# IM920Sender.net
KiCad netlist of a schematic drawn in EAGLE
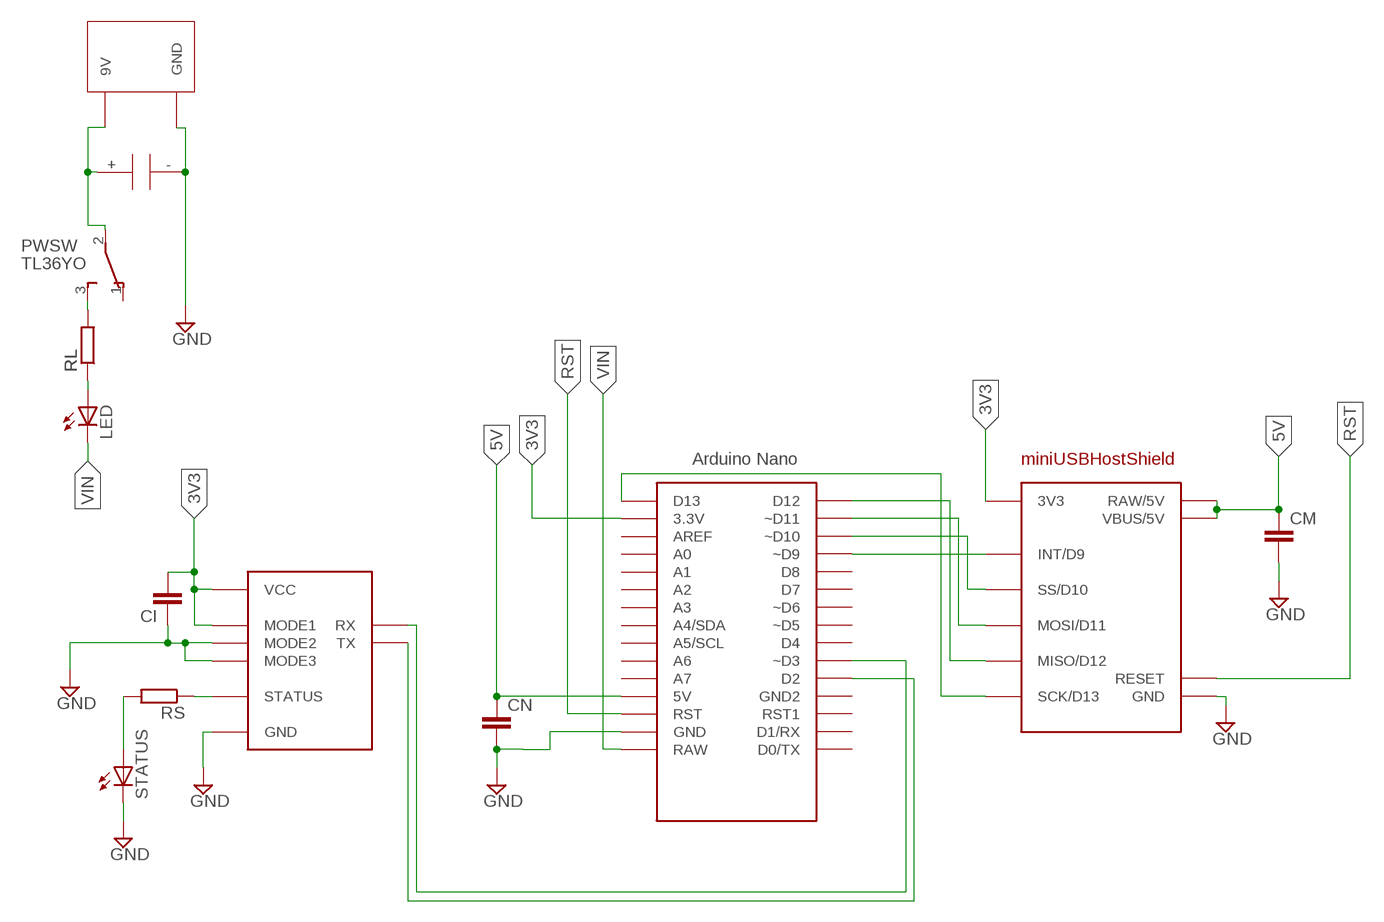
[diagram p0: schematic, sheet 1]

(export (version "E")
  (design (tool "Eeschema 10.0.6"))
  (components
    (comp (ref "CI")
      (value "C2.5/2")
      (footprint "eagle-import:C2.5-2")
      (libsource (lib "eagle-import") (part "C2.5/2"))
    )
    (comp (ref "CM")
      (value "C2.5/2")
      (footprint "eagle-import:C2.5-2")
      (libsource (lib "eagle-import") (part "C2.5/2"))
    )
    (comp (ref "CN")
      (value "C2.5/2")
      (footprint "eagle-import:C2.5-2")
      (libsource (lib "eagle-import") (part "C2.5/2"))
    )
    (comp (ref "LED")
      (value "LED3MM")
      (footprint "eagle-import:LED3MM")
      (libsource (lib "eagle-import") (part "LED3MM"))
    )
    (comp (ref "PWSW")
      (value "TL36YO")
      (footprint "eagle-import:TL3XYO")
      (libsource (lib "eagle-import") (part "TL36YO"))
    )
    (comp (ref "RL")
      (value "R-EU_0204/7")
      (footprint "eagle-import:0204_7")
      (libsource (lib "eagle-import") (part "R-EU_0204/7"))
    )
    (comp (ref "RS")
      (value "R-EU_0204/7")
      (footprint "eagle-import:0204_7")
      (libsource (lib "eagle-import") (part "R-EU_0204/7"))
    )
    (comp (ref "STATUS")
      (value "LED3MM")
      (footprint "eagle-import:LED3MM")
      (libsource (lib "eagle-import") (part "LED3MM"))
    )
    (comp (ref "U$1")
      (value "IM920")
      (footprint "eagle-import:IM920")
      (libsource (lib "eagle-import") (part "IM920"))
    )
    (comp (ref "U$2")
      (value "BH-9V-1P")
      (footprint "eagle-import:BH-9V-1P")
      (libsource (lib "eagle-import") (part "BH-9V-1P"))
    )
    (comp (ref "U$4")
      (value "MINI-USBHOSTSHIELD")
      (footprint "eagle-import:USBMINI")
      (libsource (lib "eagle-import") (part "MINI-USBHOSTSHIELD"))
    )
    (comp (ref "U$5")
      (value "C-10U")
      (footprint "eagle-import:C-10U")
      (libsource (lib "eagle-import") (part "C-10U"))
    )
    (comp (ref "U$6")
      (value "NANO")
      (footprint "eagle-import:NANO")
      (libsource (lib "eagle-import") (part "NANO"))
    )
  )
  (nets
    (net (code "1") (name "3V3") (class "Default")
      (node (ref "CI") (pin "2") (pinfunction "2_2") (pintype "passive"))
      (node (ref "U$1") (pin "MODE1") (pinfunction "MODE1_MODE1") (pintype "bidirectional"))
      (node (ref "U$1") (pin "VCC") (pinfunction "VCC_VCC") (pintype "bidirectional"))
      (node (ref "U$4") (pin "3V3") (pinfunction "3V3_3V3") (pintype "bidirectional"))
      (node (ref "U$6") (pin "3.3V") (pinfunction "3.3V_3.3V") (pintype "bidirectional"))
    )
    (net (code "2") (name "5V") (class "Default")
      (node (ref "CM") (pin "1") (pinfunction "1_1") (pintype "passive"))
      (node (ref "CN") (pin "1") (pinfunction "1_1") (pintype "passive"))
      (node (ref "U$4") (pin "RAW") (pinfunction "RAW/5V_RAW") (pintype "bidirectional"))
      (node (ref "U$4") (pin "VBUS") (pinfunction "VBUS/5V_VBUS") (pintype "bidirectional"))
      (node (ref "U$6") (pin "5V") (pinfunction "5V_5V") (pintype "bidirectional"))
    )
    (net (code "3") (name "GND") (class "Default")
      (node (ref "CI") (pin "1") (pinfunction "1_1") (pintype "passive"))
      (node (ref "CM") (pin "2") (pinfunction "2_2") (pintype "passive"))
      (node (ref "CN") (pin "2") (pinfunction "2_2") (pintype "passive"))
      (node (ref "STATUS") (pin "K") (pinfunction "C_K") (pintype "passive"))
      (node (ref "U$1") (pin "GND") (pinfunction "GND_GND") (pintype "bidirectional"))
      (node (ref "U$1") (pin "MODE2") (pinfunction "MODE2_MODE2") (pintype "bidirectional"))
      (node (ref "U$1") (pin "MODE3") (pinfunction "MODE3_MODE3") (pintype "bidirectional"))
      (node (ref "U$2") (pin "GND") (pinfunction "GND_GND") (pintype "bidirectional"))
      (node (ref "U$4") (pin "GND") (pinfunction "GND_GND") (pintype "bidirectional"))
      (node (ref "U$4") (pin "GND1") (pinfunction "GND_GND1") (pintype "bidirectional"))
      (node (ref "U$5") (pin "-") (pinfunction "-_-") (pintype "bidirectional"))
      (node (ref "U$6") (pin "GND") (pinfunction "GND_GND") (pintype "bidirectional"))
    )
    (net (code "4") (name "Net-(LED-PadA)") (class "Default")
      (node (ref "LED") (pin "A") (pinfunction "A_A") (pintype "passive"))
      (node (ref "RL") (pin "1") (pinfunction "1_1") (pintype "passive"))
    )
    (net (code "5") (name "Net-(PWSW-P)") (class "Default")
      (node (ref "PWSW") (pin "2") (pinfunction "P_2") (pintype "passive"))
      (node (ref "U$2") (pin "9V") (pinfunction "9V_9V") (pintype "bidirectional"))
      (node (ref "U$5") (pin "+") (pinfunction "+_+") (pintype "bidirectional"))
    )
    (net (code "6") (name "Net-(PWSW-S)") (class "Default")
      (node (ref "PWSW") (pin "3") (pinfunction "S_3") (pintype "passive"))
      (node (ref "RL") (pin "2") (pinfunction "2_2") (pintype "passive"))
    )
    (net (code "7") (name "Net-(RS-Pad1)") (class "Default")
      (node (ref "RS") (pin "1") (pinfunction "1_1") (pintype "passive"))
      (node (ref "U$1") (pin "STATUS") (pinfunction "STATUS_STATUS") (pintype "bidirectional"))
    )
    (net (code "8") (name "Net-(RS-Pad2)") (class "Default")
      (node (ref "RS") (pin "2") (pinfunction "2_2") (pintype "passive"))
      (node (ref "STATUS") (pin "A") (pinfunction "A_A") (pintype "passive"))
    )
    (net (code "9") (name "Net-(U$1-PadTX)") (class "Default")
      (node (ref "U$1") (pin "TX") (pinfunction "TX_TX") (pintype "bidirectional"))
      (node (ref "U$6") (pin "D2") (pinfunction "D2_D2") (pintype "bidirectional"))
    )
    (net (code "10") (name "Net-(U$4-INT{slash}D9)") (class "Default")
      (node (ref "U$4") (pin "INT") (pinfunction "INT/D9_INT") (pintype "bidirectional"))
      (node (ref "U$6") (pin "D9") (pinfunction "~{D9}_D9") (pintype "bidirectional"))
    )
    (net (code "11") (name "Net-(U$4-MISO{slash}D12)") (class "Default")
      (node (ref "U$4") (pin "MISO") (pinfunction "MISO/D12_MISO") (pintype "bidirectional"))
      (node (ref "U$6") (pin "D12") (pinfunction "D12_D12") (pintype "bidirectional"))
    )
    (net (code "12") (name "Net-(U$4-MOSI{slash}D11)") (class "Default")
      (node (ref "U$4") (pin "MOSI") (pinfunction "MOSI/D11_MOSI") (pintype "bidirectional"))
      (node (ref "U$6") (pin "D11") (pinfunction "~{D11}_D11") (pintype "bidirectional"))
    )
    (net (code "13") (name "Net-(U$4-SCK{slash}D13)") (class "Default")
      (node (ref "U$4") (pin "SCK") (pinfunction "SCK/D13_SCK") (pintype "bidirectional"))
      (node (ref "U$6") (pin "D13") (pinfunction "D13_D13") (pintype "bidirectional"))
    )
    (net (code "14") (name "Net-(U$4-SS{slash}D10)") (class "Default")
      (node (ref "U$4") (pin "SS") (pinfunction "SS/D10_SS") (pintype "bidirectional"))
      (node (ref "U$6") (pin "D10") (pinfunction "~{D10}_D10") (pintype "bidirectional"))
    )
    (net (code "15") (name "Net-(U$6-~{D3})") (class "Default")
      (node (ref "U$1") (pin "RX") (pinfunction "RX_RX") (pintype "bidirectional"))
      (node (ref "U$6") (pin "D3") (pinfunction "~{D3}_D3") (pintype "bidirectional"))
    )
    (net (code "16") (name "RST") (class "Default")
      (node (ref "U$4") (pin "RESET") (pinfunction "RESET_RESET") (pintype "bidirectional"))
      (node (ref "U$6") (pin "RST") (pinfunction "RST_RST") (pintype "bidirectional"))
    )
    (net (code "17") (name "VIN") (class "Default")
      (node (ref "LED") (pin "K") (pinfunction "C_K") (pintype "passive"))
      (node (ref "U$6") (pin "RAW") (pinfunction "RAW_RAW") (pintype "bidirectional"))
    )
    (net (code "18") (name "unconnected-(PWSW-O-Pad1)") (class "Default")
      (node (ref "PWSW") (pin "1") (pinfunction "O_1") (pintype "passive"))
    )
    (net (code "19") (name "unconnected-(U$6-A4{slash}SDA-PadA4)") (class "Default")
      (node (ref "U$6") (pin "A4") (pinfunction "A4/SDA_A4") (pintype "bidirectional"))
    )
    (net (code "20") (name "unconnected-(U$6-A5{slash}SCL-PadA5)") (class "Default")
      (node (ref "U$6") (pin "A5") (pinfunction "A5/SCL_A5") (pintype "bidirectional"))
    )
    (net (code "21") (name "unconnected-(U$6-D0{slash}TX-PadTX0)") (class "Default")
      (node (ref "U$6") (pin "TX0") (pinfunction "D0/TX_TX0") (pintype "bidirectional"))
    )
    (net (code "22") (name "unconnected-(U$6-D1{slash}RX-PadRX1)") (class "Default")
      (node (ref "U$6") (pin "RX1") (pinfunction "D1/RX_RX1") (pintype "bidirectional"))
    )
    (net (code "23") (name "unconnected-(U$6-GND2-PadGND1)") (class "Default")
      (node (ref "U$6") (pin "GND1") (pinfunction "GND2_GND1") (pintype "bidirectional"))
    )
    (net (code "24") (name "unconnected-(U$6-PadA0)") (class "Default")
      (node (ref "U$6") (pin "A0") (pinfunction "A0_A0") (pintype "bidirectional"))
    )
    (net (code "25") (name "unconnected-(U$6-PadA1)") (class "Default")
      (node (ref "U$6") (pin "A1") (pinfunction "A1_A1") (pintype "bidirectional"))
    )
    (net (code "26") (name "unconnected-(U$6-PadA2)") (class "Default")
      (node (ref "U$6") (pin "A2") (pinfunction "A2_A2") (pintype "bidirectional"))
    )
    (net (code "27") (name "unconnected-(U$6-PadA3)") (class "Default")
      (node (ref "U$6") (pin "A3") (pinfunction "A3_A3") (pintype "bidirectional"))
    )
    (net (code "28") (name "unconnected-(U$6-PadA6)") (class "Default")
      (node (ref "U$6") (pin "A6") (pinfunction "A6_A6") (pintype "bidirectional"))
    )
    (net (code "29") (name "unconnected-(U$6-PadA7)") (class "Default")
      (node (ref "U$6") (pin "A7") (pinfunction "A7_A7") (pintype "bidirectional"))
    )
    (net (code "30") (name "unconnected-(U$6-PadAREF)") (class "Default")
      (node (ref "U$6") (pin "AREF") (pinfunction "AREF_AREF") (pintype "bidirectional"))
    )
    (net (code "31") (name "unconnected-(U$6-PadD4)") (class "Default")
      (node (ref "U$6") (pin "D4") (pinfunction "D4_D4") (pintype "bidirectional"))
    )
    (net (code "32") (name "unconnected-(U$6-PadD7)") (class "Default")
      (node (ref "U$6") (pin "D7") (pinfunction "D7_D7") (pintype "bidirectional"))
    )
    (net (code "33") (name "unconnected-(U$6-PadD8)") (class "Default")
      (node (ref "U$6") (pin "D8") (pinfunction "D8_D8") (pintype "bidirectional"))
    )
    (net (code "34") (name "unconnected-(U$6-PadRST1)") (class "Default")
      (node (ref "U$6") (pin "RST1") (pinfunction "RST1_RST1") (pintype "bidirectional"))
    )
    (net (code "35") (name "unconnected-(U$6-~{D5}-PadD5)") (class "Default")
      (node (ref "U$6") (pin "D5") (pinfunction "~{D5}_D5") (pintype "bidirectional"))
    )
    (net (code "36") (name "unconnected-(U$6-~{D6}-PadD6)") (class "Default")
      (node (ref "U$6") (pin "D6") (pinfunction "~{D6}_D6") (pintype "bidirectional"))
    )
  )
)
